# Picocopter_Edit.net
KiCad netlist of a schematic drawn in Altium Designer
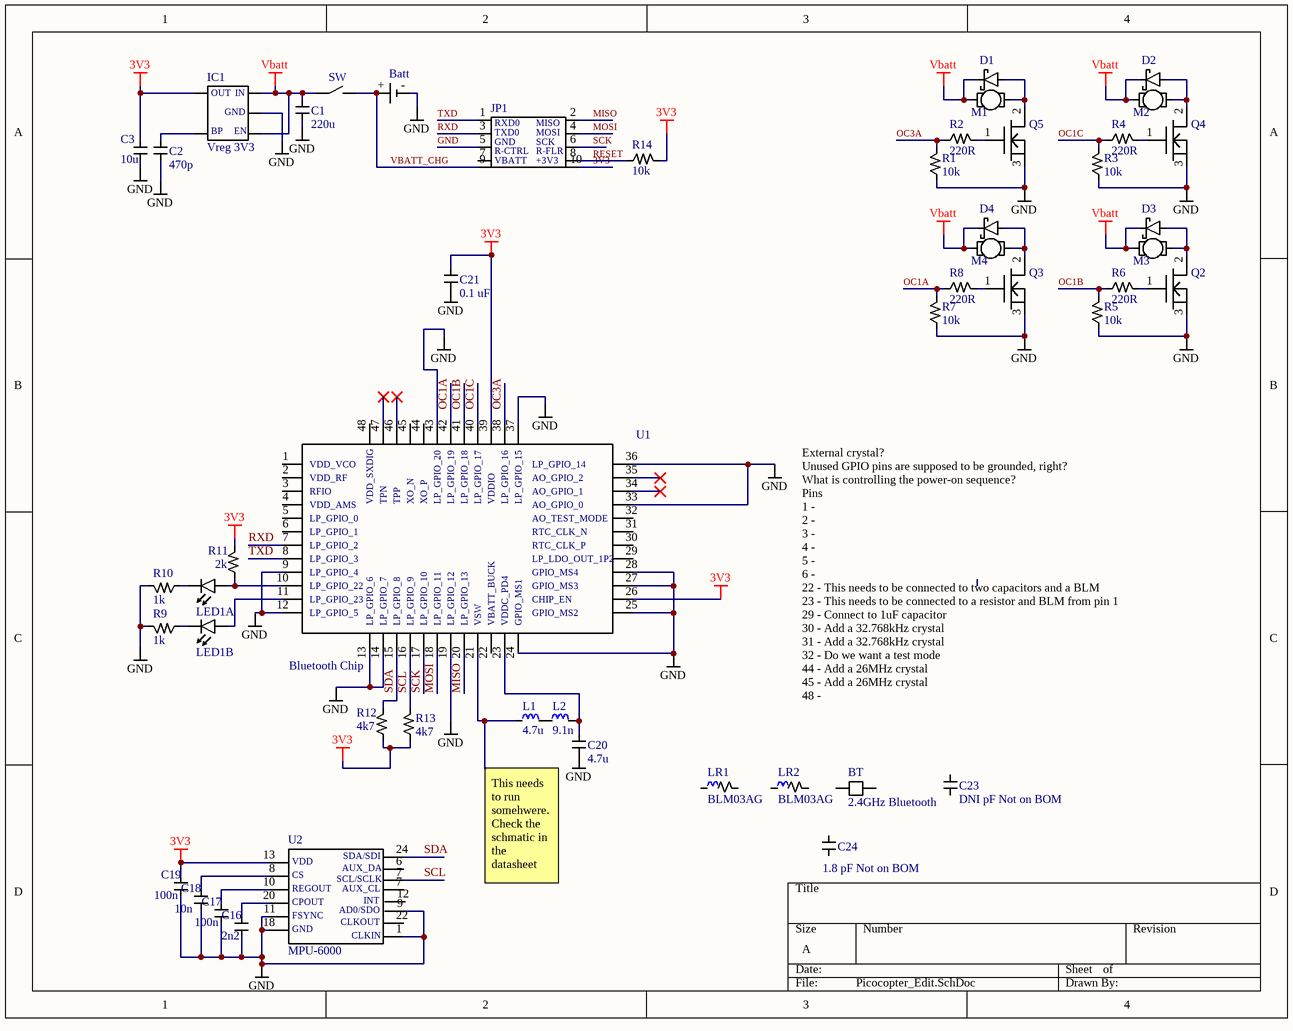
[diagram p0: Picocopter_Edit.SchDoc]

(export (version "E")
  (design (tool "Eeschema 10.0.6"))
  (components
    (comp (ref "Batt") (value "Battery") (footprint "Battery") (libsource (lib "Battery") (part "Battery")))
    (comp (ref "BT")
      (value "2.4GHz Bluetooth")
      (footprint "2.4GHz Bluetooth")
      (libsource (lib "2.4GHz Bluetooth") (part "2.4GHz Bluetooth"))
    )
    (comp (ref "C1")
      (value "220u")
      (footprint "1206 Capacitor")
      (libsource (lib "1206 Capacitor") (part "1206 Capacitor"))
    )
    (comp (ref "C2")
      (value "470p")
      (footprint "0201 Capacitor")
      (libsource (lib "0201 Capacitor") (part "10 pF Capacitor"))
    )
    (comp (ref "C3")
      (value "10u")
      (footprint "0402 Capacitor")
      (libsource (lib "0402 Capacitor") (part "0402 Capacitor"))
    )
    (comp (ref "C16")
      (value "2n2")
      (footprint "0603 Capacitor")
      (libsource (lib "0603 Capacitor") (part "0603 Capacitor"))
    )
    (comp (ref "C17")
      (value "100n")
      (footprint "0603 Capacitor")
      (libsource (lib "0603 Capacitor") (part "0603 Capacitor"))
    )
    (comp (ref "C18")
      (value "10n")
      (footprint "0603 Capacitor")
      (libsource (lib "0603 Capacitor") (part "0603 Capacitor"))
    )
    (comp (ref "C19")
      (value "100n")
      (footprint "0603 Capacitor")
      (libsource (lib "0603 Capacitor") (part "0603 Capacitor"))
    )
    (comp (ref "C20")
      (value "4.7u")
      (footprint "0603 Capacitor")
      (libsource (lib "0603 Capacitor") (part "0603 Capacitor"))
    )
    (comp (ref "C21")
      (value "0.1 uF")
      (footprint "0201 Capacitor")
      (libsource (lib "0201 Capacitor") (part "10 pF Capacitor"))
    )
    (comp (ref "C23")
      (value "DNI pF Not on BOM")
      (footprint "0201 Capacitor")
      (libsource (lib "0201 Capacitor") (part "10 pF Capacitor"))
    )
    (comp (ref "C24")
      (value "1.8 pF Not on BOM")
      (footprint "0201 Capacitor")
      (libsource (lib "0201 Capacitor") (part "10 pF Capacitor"))
    )
    (comp (ref "D1")
      (value "Schottky Diode")
      (footprint "Schottky Diode")
      (libsource (lib "Schottky Diode") (part "Schottky Diode"))
    )
    (comp (ref "D2")
      (value "Schottky Diode")
      (footprint "Schottky Diode")
      (libsource (lib "Schottky Diode") (part "Schottky Diode"))
    )
    (comp (ref "D3")
      (value "Schottky Diode")
      (footprint "Schottky Diode")
      (libsource (lib "Schottky Diode") (part "Schottky Diode"))
    )
    (comp (ref "D4")
      (value "Schottky Diode")
      (footprint "Schottky Diode")
      (libsource (lib "Schottky Diode") (part "Schottky Diode"))
    )
    (comp (ref "IC1")
      (value "Vreg 3V3")
      (footprint "Voltage Regulator")
      (libsource (lib "Voltage Regulator") (part "Voltage Regulator"))
    )
    (comp (ref "JP1")
      (value "10 Pin Connector")
      (footprint "10 Pin Connector")
      (libsource (lib "10 Pin Connector") (part "10 Pin Connector"))
    )
    (comp (ref "L1")
      (value "4.7u")
      (footprint "INDC2924X10N")
      (libsource (lib "1008 Inductor") (part "Component_1"))
    )
    (comp (ref "L2")
      (value "9.1n")
      (footprint "PCBComponent_1 - duplicate")
      (libsource (lib "0402 Inductor") (part "Component_1"))
    )
    (comp (ref "LED1A")
      (value "PicoLED")
      (footprint "DFN70P60X45-2N")
      (libsource (lib "PicoLED") (part "PicoLED"))
    )
    (comp (ref "LED1B")
      (value "PicoLED")
      (footprint "DFN70P60X45-2N")
      (libsource (lib "PicoLED") (part "PicoLED"))
    )
    (comp (ref "LR1")
      (value "BLM03AG")
      (footprint "INDC0603X10N")
      (libsource (lib "BLM03AG Resistive Inductor") (part "Component_1"))
    )
    (comp (ref "LR2")
      (value "BLM03AG")
      (footprint "INDC0603X10N")
      (libsource (lib "BLM03AG Resistive Inductor") (part "Component_1"))
    )
    (comp (ref "M1") (value "Motor") (footprint "Battery") (libsource (lib "Motor") (part "Motor")))
    (comp (ref "M2") (value "Motor") (footprint "Battery") (libsource (lib "Motor") (part "Motor")))
    (comp (ref "M3") (value "Motor") (footprint "Battery") (libsource (lib "Motor") (part "Motor")))
    (comp (ref "M4") (value "Motor") (footprint "Battery") (libsource (lib "Motor") (part "Motor")))
    (comp (ref "Q2")
      (value "N-Channel MOSFET")
      (footprint "N-Channel MOSFET")
      (libsource (lib "N-Channel MOSFET") (part "N-Channel MOSFET"))
    )
    (comp (ref "Q3")
      (value "N-Channel MOSFET")
      (footprint "N-Channel MOSFET")
      (libsource (lib "N-Channel MOSFET") (part "N-Channel MOSFET"))
    )
    (comp (ref "Q4")
      (value "N-Channel MOSFET")
      (footprint "N-Channel MOSFET")
      (libsource (lib "N-Channel MOSFET") (part "N-Channel MOSFET"))
    )
    (comp (ref "Q5")
      (value "MOSFET")
      (footprint "N-Channel MOSFET")
      (libsource (lib "N-Channel MOSFET") (part "N-Channel MOSFET"))
    )
    (comp (ref "R1")
      (value "10k")
      (footprint "0402 Resistor")
      (libsource (lib "0402 Resistor") (part "0402 Resistor"))
    )
    (comp (ref "R2")
      (value "220R")
      (footprint "0402 Resistor")
      (libsource (lib "0402 Resistor") (part "0402 Resistor"))
    )
    (comp (ref "R3")
      (value "10k")
      (footprint "0402 Resistor")
      (libsource (lib "0402 Resistor") (part "0402 Resistor"))
    )
    (comp (ref "R4")
      (value "220R")
      (footprint "0402 Resistor")
      (libsource (lib "0402 Resistor") (part "0402 Resistor"))
    )
    (comp (ref "R5")
      (value "10k")
      (footprint "0402 Resistor")
      (libsource (lib "0402 Resistor") (part "0402 Resistor"))
    )
    (comp (ref "R6")
      (value "220R")
      (footprint "0402 Resistor")
      (libsource (lib "0402 Resistor") (part "0402 Resistor"))
    )
    (comp (ref "R7")
      (value "10k")
      (footprint "0402 Resistor")
      (libsource (lib "0402 Resistor") (part "0402 Resistor"))
    )
    (comp (ref "R8")
      (value "220R")
      (footprint "0402 Resistor")
      (libsource (lib "0402 Resistor") (part "0402 Resistor"))
    )
    (comp (ref "R9")
      (value "1k")
      (footprint "0402 Resistor")
      (libsource (lib "0402 Resistor") (part "0402 Resistor"))
    )
    (comp (ref "R10")
      (value "1k")
      (footprint "0402 Resistor")
      (libsource (lib "0402 Resistor") (part "0402 Resistor"))
    )
    (comp (ref "R11")
      (value "2k")
      (footprint "0402 Resistor")
      (libsource (lib "0402 Resistor") (part "0402 Resistor"))
    )
    (comp (ref "R12")
      (value "4k7")
      (footprint "0402 Resistor")
      (libsource (lib "0402 Resistor") (part "0402 Resistor"))
    )
    (comp (ref "R13")
      (value "4k7")
      (footprint "0402 Resistor")
      (libsource (lib "0402 Resistor") (part "0402 Resistor"))
    )
    (comp (ref "R14")
      (value "10k")
      (footprint "0402 Resistor")
      (libsource (lib "0402 Resistor") (part "0402 Resistor"))
    )
    (comp (ref "SW")
      (value "2 Pin Header")
      (footprint "2 Pin Header")
      (libsource (lib "2 Pin Header") (part "2 Pin Header"))
    )
    (comp (ref "U1")
      (value "Bluetooth Chip")
      (footprint "QFN40P600X600X10_HS-49N")
      (libsource (lib "Bluetooth Chip") (part "Component_1"))
    )
    (comp (ref "U2")
      (value "MPU-6000")
      (footprint "Accelerometer")
      (libsource (lib "Accelerometer") (part "Accelerometer"))
    )
  )
  (nets
    (net (code "1") (name "/MISO") (class "Default")
      (node (ref "JP1") (pin "2") (pinfunction "2_2") (pintype "passive"))
      (node (ref "U1") (pin "20") (pinfunction "20_20") (pintype "passive"))
    )
    (net (code "2") (name "/MOSI") (class "Default")
      (node (ref "JP1") (pin "4") (pinfunction "4_4") (pintype "passive"))
      (node (ref "U1") (pin "18") (pinfunction "18_18") (pintype "passive"))
    )
    (net (code "3") (name "/OC1A") (class "Default")
      (node (ref "R7") (pin "2") (pinfunction "2_2") (pintype "passive"))
      (node (ref "R8") (pin "1") (pinfunction "1_1") (pintype "passive"))
      (node (ref "U1") (pin "42") (pinfunction "42_42") (pintype "passive"))
    )
    (net (code "4") (name "/OC1B") (class "Default")
      (node (ref "R5") (pin "2") (pinfunction "2_2") (pintype "passive"))
      (node (ref "R6") (pin "1") (pinfunction "1_1") (pintype "passive"))
      (node (ref "U1") (pin "41") (pinfunction "41_41") (pintype "passive"))
    )
    (net (code "5") (name "/OC1C") (class "Default")
      (node (ref "R3") (pin "2") (pinfunction "2_2") (pintype "passive"))
      (node (ref "R4") (pin "1") (pinfunction "1_1") (pintype "passive"))
      (node (ref "U1") (pin "40") (pinfunction "40_40") (pintype "passive"))
    )
    (net (code "6") (name "/OC3A") (class "Default")
      (node (ref "R1") (pin "2") (pinfunction "2_2") (pintype "passive"))
      (node (ref "R2") (pin "1") (pinfunction "1_1") (pintype "passive"))
      (node (ref "U1") (pin "38") (pinfunction "38_38") (pintype "passive"))
    )
    (net (code "7") (name "/RESET") (class "Default")
      (node (ref "JP1") (pin "8") (pinfunction "8_8") (pintype "passive"))
      (node (ref "R14") (pin "1") (pinfunction "1_1") (pintype "passive"))
    )
    (net (code "8") (name "/RXD") (class "Default")
      (node (ref "JP1") (pin "3") (pinfunction "3_3") (pintype "passive"))
      (node (ref "U1") (pin "7") (pinfunction "7_7") (pintype "passive"))
    )
    (net (code "9") (name "/SCK") (class "Default")
      (node (ref "JP1") (pin "6") (pinfunction "6_6") (pintype "passive"))
      (node (ref "U1") (pin "17") (pinfunction "17_17") (pintype "passive"))
    )
    (net (code "10") (name "/SCL") (class "Default")
      (node (ref "R13") (pin "2") (pinfunction "2_2") (pintype "passive"))
      (node (ref "U1") (pin "16") (pinfunction "16_16") (pintype "passive"))
      (node (ref "U2") (pin "7") (pinfunction "7_7") (pintype "passive"))
    )
    (net (code "11") (name "/SDA") (class "Default")
      (node (ref "R12") (pin "2") (pinfunction "2_2") (pintype "passive"))
      (node (ref "U1") (pin "15") (pinfunction "15_15") (pintype "passive"))
      (node (ref "U2") (pin "24") (pinfunction "24_24") (pintype "passive"))
    )
    (net (code "12") (name "/TXD") (class "Default")
      (node (ref "JP1") (pin "1") (pinfunction "1_1") (pintype "passive"))
      (node (ref "U1") (pin "8") (pinfunction "8_8") (pintype "passive"))
    )
    (net (code "13") (name "/VBATT_CHG") (class "Default")
      (node (ref "Batt") (pin "+") (pinfunction "7_+") (pintype "passive"))
      (node (ref "JP1") (pin "9") (pinfunction "9_9") (pintype "passive"))
      (node (ref "SW") (pin "6") (pinfunction "6_6") (pintype "passive"))
    )
    (net (code "14") (name "3V3") (class "Default")
      (node (ref "C19") (pin "2") (pinfunction "2_2") (pintype "passive"))
      (node (ref "C21") (pin "1") (pinfunction "1_1") (pintype "passive"))
      (node (ref "C3") (pin "2") (pinfunction "2_2") (pintype "passive"))
      (node (ref "IC1") (pin "1") (pinfunction "1_1") (pintype "passive"))
      (node (ref "JP1") (pin "10") (pinfunction "10_10") (pintype "passive"))
      (node (ref "R11") (pin "2") (pinfunction "2_2") (pintype "passive"))
      (node (ref "R12") (pin "1") (pinfunction "1_1") (pintype "passive"))
      (node (ref "R13") (pin "1") (pinfunction "1_1") (pintype "passive"))
      (node (ref "R14") (pin "2") (pinfunction "2_2") (pintype "passive"))
      (node (ref "U1") (pin "26") (pinfunction "26_26") (pintype "passive"))
      (node (ref "U1") (pin "39") (pinfunction "39_39") (pintype "passive"))
      (node (ref "U2") (pin "13") (pinfunction "13_13") (pintype "passive"))
    )
    (net (code "15") (name "GND") (class "Default")
      (node (ref "Batt") (pin "-") (pinfunction "8_-") (pintype "passive"))
      (node (ref "C1") (pin "1") (pinfunction "1_1") (pintype "passive"))
      (node (ref "C16") (pin "1") (pinfunction "1_1") (pintype "passive"))
      (node (ref "C17") (pin "1") (pinfunction "1_1") (pintype "passive"))
      (node (ref "C18") (pin "1") (pinfunction "1_1") (pintype "passive"))
      (node (ref "C19") (pin "1") (pinfunction "1_1") (pintype "passive"))
      (node (ref "C2") (pin "1") (pinfunction "1_1") (pintype "passive"))
      (node (ref "C20") (pin "1") (pinfunction "1_1") (pintype "passive"))
      (node (ref "C21") (pin "2") (pinfunction "2_2") (pintype "passive"))
      (node (ref "C3") (pin "1") (pinfunction "1_1") (pintype "passive"))
      (node (ref "IC1") (pin "4") (pinfunction "4_4") (pintype "passive"))
      (node (ref "JP1") (pin "5") (pinfunction "5_5") (pintype "passive"))
      (node (ref "Q2") (pin "3") (pinfunction "3_3") (pintype "passive"))
      (node (ref "Q3") (pin "3") (pinfunction "3_3") (pintype "passive"))
      (node (ref "Q4") (pin "3") (pinfunction "3_3") (pintype "passive"))
      (node (ref "Q5") (pin "3") (pinfunction "3_3") (pintype "passive"))
      (node (ref "R1") (pin "1") (pinfunction "1_1") (pintype "passive"))
      (node (ref "R10") (pin "2") (pinfunction "2_2") (pintype "passive"))
      (node (ref "R3") (pin "1") (pinfunction "1_1") (pintype "passive"))
      (node (ref "R5") (pin "1") (pinfunction "1_1") (pintype "passive"))
      (node (ref "R7") (pin "1") (pinfunction "1_1") (pintype "passive"))
      (node (ref "R9") (pin "2") (pinfunction "2_2") (pintype "passive"))
      (node (ref "U1") (pin "12") (pinfunction "12_12") (pintype "passive"))
      (node (ref "U1") (pin "13") (pinfunction "13_13") (pintype "passive"))
      (node (ref "U1") (pin "14") (pinfunction "14_14") (pintype "passive"))
      (node (ref "U1") (pin "19") (pinfunction "19_19") (pintype "passive"))
      (node (ref "U1") (pin "24") (pinfunction "24_24") (pintype "passive"))
      (node (ref "U1") (pin "25") (pinfunction "25_25") (pintype "passive"))
      (node (ref "U1") (pin "27") (pinfunction "27_27") (pintype "passive"))
      (node (ref "U1") (pin "28") (pinfunction "28_28") (pintype "passive"))
      (node (ref "U1") (pin "33") (pinfunction "33_33") (pintype "passive"))
      (node (ref "U1") (pin "36") (pinfunction "36_36") (pintype "passive"))
      (node (ref "U1") (pin "37") (pinfunction "37_37") (pintype "passive"))
      (node (ref "U1") (pin "43") (pinfunction "43_43") (pintype "passive"))
      (node (ref "U1") (pin "9") (pinfunction "9_9") (pintype "passive"))
      (node (ref "U2") (pin "1") (pinfunction "1_1") (pintype "passive"))
      (node (ref "U2") (pin "11") (pinfunction "11_11") (pintype "passive"))
      (node (ref "U2") (pin "18") (pinfunction "18_18") (pintype "passive"))
      (node (ref "U2") (pin "9") (pinfunction "9_9") (pintype "passive"))
    )
    (net (code "16") (name "Net-(C2-Pad2)") (class "Default")
      (node (ref "C2") (pin "2") (pinfunction "2_2") (pintype "passive"))
      (node (ref "IC1") (pin "2") (pinfunction "2_2") (pintype "passive"))
    )
    (net (code "17") (name "Net-(C16-Pad2)") (class "Default")
      (node (ref "C16") (pin "2") (pinfunction "2_2") (pintype "passive"))
      (node (ref "U2") (pin "20") (pinfunction "20_20") (pintype "passive"))
    )
    (net (code "18") (name "Net-(C17-Pad2)") (class "Default")
      (node (ref "C17") (pin "2") (pinfunction "2_2") (pintype "passive"))
      (node (ref "U2") (pin "10") (pinfunction "10_10") (pintype "passive"))
    )
    (net (code "19") (name "Net-(C18-Pad2)") (class "Default")
      (node (ref "C18") (pin "2") (pinfunction "2_2") (pintype "passive"))
      (node (ref "U2") (pin "8") (pinfunction "8_8") (pintype "passive"))
    )
    (net (code "20") (name "Net-(C20-Pad2)") (class "Default")
      (node (ref "C20") (pin "2") (pinfunction "2_2") (pintype "passive"))
      (node (ref "L2") (pin "0") (pinfunction "0_0") (pintype "passive"))
      (node (ref "U1") (pin "23") (pinfunction "23_23") (pintype "passive"))
    )
    (net (code "21") (name "Net-(D1-Pad1)") (class "Default")
      (node (ref "D1") (pin "1") (pinfunction "1_1") (pintype "passive"))
      (node (ref "M1") (pin "4") (pinfunction "4_4") (pintype "passive"))
      (node (ref "Q5") (pin "2") (pinfunction "2_2") (pintype "passive"))
    )
    (net (code "22") (name "Net-(D2-Pad1)") (class "Default")
      (node (ref "D2") (pin "1") (pinfunction "1_1") (pintype "passive"))
      (node (ref "M2") (pin "4") (pinfunction "4_4") (pintype "passive"))
      (node (ref "Q4") (pin "2") (pinfunction "2_2") (pintype "passive"))
    )
    (net (code "23") (name "Net-(D3-Pad1)") (class "Default")
      (node (ref "D3") (pin "1") (pinfunction "1_1") (pintype "passive"))
      (node (ref "M3") (pin "4") (pinfunction "4_4") (pintype "passive"))
      (node (ref "Q2") (pin "2") (pinfunction "2_2") (pintype "passive"))
    )
    (net (code "24") (name "Net-(D4-Pad1)") (class "Default")
      (node (ref "D4") (pin "1") (pinfunction "1_1") (pintype "passive"))
      (node (ref "M4") (pin "4") (pinfunction "4_4") (pintype "passive"))
      (node (ref "Q3") (pin "2") (pinfunction "2_2") (pintype "passive"))
    )
    (net (code "25") (name "Net-(L1-Pad0)") (class "Default")
      (node (ref "L1") (pin "0") (pinfunction "0_0") (pintype "passive"))
      (node (ref "L2") (pin "1") (pinfunction "1_1") (pintype "passive"))
    )
    (net (code "26") (name "Net-(L1-Pad1)") (class "Default")
      (node (ref "L1") (pin "1") (pinfunction "1_1") (pintype "passive"))
      (node (ref "U1") (pin "21") (pinfunction "21_21") (pintype "passive"))
    )
    (net (code "27") (name "Net-(LED1A-Pad1)") (class "Default")
      (node (ref "LED1A") (pin "1") (pinfunction "1_1") (pintype "passive"))
      (node (ref "R11") (pin "1") (pinfunction "1_1") (pintype "passive"))
      (node (ref "U1") (pin "10") (pinfunction "10_10") (pintype "passive"))
    )
    (net (code "28") (name "Net-(LED1A-Pad2)") (class "Default")
      (node (ref "LED1A") (pin "2") (pinfunction "2_2") (pintype "passive"))
      (node (ref "R10") (pin "1") (pinfunction "1_1") (pintype "passive"))
    )
    (net (code "29") (name "Net-(LED1B-Pad1)") (class "Default")
      (node (ref "LED1B") (pin "1") (pinfunction "1_1") (pintype "passive"))
      (node (ref "U1") (pin "11") (pinfunction "11_11") (pintype "passive"))
    )
    (net (code "30") (name "Net-(LED1B-Pad2)") (class "Default")
      (node (ref "LED1B") (pin "2") (pinfunction "2_2") (pintype "passive"))
      (node (ref "R9") (pin "1") (pinfunction "1_1") (pintype "passive"))
    )
    (net (code "31") (name "Net-(Q2-Pad1)") (class "Default")
      (node (ref "Q2") (pin "1") (pinfunction "1_1") (pintype "passive"))
      (node (ref "R6") (pin "2") (pinfunction "2_2") (pintype "passive"))
    )
    (net (code "32") (name "Net-(Q3-Pad1)") (class "Default")
      (node (ref "Q3") (pin "1") (pinfunction "1_1") (pintype "passive"))
      (node (ref "R8") (pin "2") (pinfunction "2_2") (pintype "passive"))
    )
    (net (code "33") (name "Net-(Q4-Pad1)") (class "Default")
      (node (ref "Q4") (pin "1") (pinfunction "1_1") (pintype "passive"))
      (node (ref "R4") (pin "2") (pinfunction "2_2") (pintype "passive"))
    )
    (net (code "34") (name "Net-(Q5-Pad1)") (class "Default")
      (node (ref "Q5") (pin "1") (pinfunction "1_1") (pintype "passive"))
      (node (ref "R2") (pin "2") (pinfunction "2_2") (pintype "passive"))
    )
    (net (code "35") (name "Vbatt") (class "Default")
      (node (ref "C1") (pin "2") (pinfunction "2_2") (pintype "passive"))
      (node (ref "D1") (pin "2") (pinfunction "2_2") (pintype "passive"))
      (node (ref "D2") (pin "2") (pinfunction "2_2") (pintype "passive"))
      (node (ref "D3") (pin "2") (pinfunction "2_2") (pintype "passive"))
      (node (ref "D4") (pin "2") (pinfunction "2_2") (pintype "passive"))
      (node (ref "IC1") (pin "3") (pinfunction "3_3") (pintype "passive"))
      (node (ref "IC1") (pin "5") (pinfunction "5_5") (pintype "passive"))
      (node (ref "M1") (pin "3") (pinfunction "3_3") (pintype "passive"))
      (node (ref "M2") (pin "3") (pinfunction "3_3") (pintype "passive"))
      (node (ref "M3") (pin "3") (pinfunction "3_3") (pintype "passive"))
      (node (ref "M4") (pin "3") (pinfunction "3_3") (pintype "passive"))
      (node (ref "SW") (pin "5") (pinfunction "5_5") (pintype "passive"))
    )
    (net (code "36") (name "unconnected-(BT-Pad1)") (class "Default")
      (node (ref "BT") (pin "1") (pinfunction "1_1") (pintype "passive"))
    )
    (net (code "37") (name "unconnected-(BT-Pad2)") (class "Default")
      (node (ref "BT") (pin "2") (pinfunction "2_2") (pintype "passive"))
    )
    (net (code "38") (name "unconnected-(C23-Pad1)") (class "Default")
      (node (ref "C23") (pin "1") (pinfunction "1_1") (pintype "passive"))
    )
    (net (code "39") (name "unconnected-(C23-Pad2)") (class "Default")
      (node (ref "C23") (pin "2") (pinfunction "2_2") (pintype "passive"))
    )
    (net (code "40") (name "unconnected-(C24-Pad1)") (class "Default")
      (node (ref "C24") (pin "1") (pinfunction "1_1") (pintype "passive"))
    )
    (net (code "41") (name "unconnected-(C24-Pad2)") (class "Default")
      (node (ref "C24") (pin "2") (pinfunction "2_2") (pintype "passive"))
    )
    (net (code "42") (name "unconnected-(JP1-Pad7)") (class "Default")
      (node (ref "JP1") (pin "7") (pinfunction "7_7") (pintype "passive"))
    )
    (net (code "43") (name "unconnected-(LR1-Pad0)") (class "Default")
      (node (ref "LR1") (pin "0") (pinfunction "0_0") (pintype "passive"))
    )
    (net (code "44") (name "unconnected-(LR1-Pad1)") (class "Default")
      (node (ref "LR1") (pin "1") (pinfunction "1_1") (pintype "passive"))
    )
    (net (code "45") (name "unconnected-(LR2-Pad0)") (class "Default")
      (node (ref "LR2") (pin "0") (pinfunction "0_0") (pintype "passive"))
    )
    (net (code "46") (name "unconnected-(LR2-Pad1)") (class "Default")
      (node (ref "LR2") (pin "1") (pinfunction "1_1") (pintype "passive"))
    )
    (net (code "47") (name "unconnected-(U1-Pad1)") (class "Default")
      (node (ref "U1") (pin "1") (pinfunction "1_1") (pintype "passive"))
    )
    (net (code "48") (name "unconnected-(U1-Pad2)") (class "Default")
      (node (ref "U1") (pin "2") (pinfunction "2_2") (pintype "passive"))
    )
    (net (code "49") (name "unconnected-(U1-Pad3)") (class "Default")
      (node (ref "U1") (pin "3") (pinfunction "3_3") (pintype "passive"))
    )
    (net (code "50") (name "unconnected-(U1-Pad4)") (class "Default")
      (node (ref "U1") (pin "4") (pinfunction "4_4") (pintype "passive"))
    )
    (net (code "51") (name "unconnected-(U1-Pad5)") (class "Default")
      (node (ref "U1") (pin "5") (pinfunction "5_5") (pintype "passive"))
    )
    (net (code "52") (name "unconnected-(U1-Pad6)") (class "Default")
      (node (ref "U1") (pin "6") (pinfunction "6_6") (pintype "passive"))
    )
    (net (code "53") (name "unconnected-(U1-Pad22)") (class "Default")
      (node (ref "U1") (pin "22") (pinfunction "22_22") (pintype "passive"))
    )
    (net (code "54") (name "unconnected-(U1-Pad29)") (class "Default")
      (node (ref "U1") (pin "29") (pinfunction "29_29") (pintype "passive"))
    )
    (net (code "55") (name "unconnected-(U1-Pad30)") (class "Default")
      (node (ref "U1") (pin "30") (pinfunction "30_30") (pintype "passive"))
    )
    (net (code "56") (name "unconnected-(U1-Pad31)") (class "Default")
      (node (ref "U1") (pin "31") (pinfunction "31_31") (pintype "passive"))
    )
    (net (code "57") (name "unconnected-(U1-Pad32)") (class "Default")
      (node (ref "U1") (pin "32") (pinfunction "32_32") (pintype "passive"))
    )
    (net (code "58") (name "unconnected-(U1-Pad34)") (class "Default")
      (node (ref "U1") (pin "34") (pinfunction "34_34") (pintype "passive+no_connect"))
    )
    (net (code "59") (name "unconnected-(U1-Pad35)") (class "Default")
      (node (ref "U1") (pin "35") (pinfunction "35_35") (pintype "passive+no_connect"))
    )
    (net (code "60") (name "unconnected-(U1-Pad44)") (class "Default")
      (node (ref "U1") (pin "44") (pinfunction "44_44") (pintype "passive"))
    )
    (net (code "61") (name "unconnected-(U1-Pad45)") (class "Default")
      (node (ref "U1") (pin "45") (pinfunction "45_45") (pintype "passive"))
    )
    (net (code "62") (name "unconnected-(U1-Pad46)") (class "Default")
      (node (ref "U1") (pin "46") (pinfunction "46_46") (pintype "passive+no_connect"))
    )
    (net (code "63") (name "unconnected-(U1-Pad47)") (class "Default")
      (node (ref "U1") (pin "47") (pinfunction "47_47") (pintype "passive+no_connect"))
    )
    (net (code "64") (name "unconnected-(U1-Pad48)") (class "Default")
      (node (ref "U1") (pin "48") (pinfunction "48_48") (pintype "passive"))
    )
    (net (code "65") (name "unconnected-(U2-Pad6)") (class "Default")
      (node (ref "U2") (pin "6") (pinfunction "6_6") (pintype "passive"))
    )
    (net (code "66") (name "unconnected-(U2-Pad7)") (class "Default")
      (node (ref "U2") (pin "7") (pinfunction "7_7") (pintype "passive"))
    )
    (net (code "67") (name "unconnected-(U2-Pad12)") (class "Default")
      (node (ref "U2") (pin "12") (pinfunction "12_12") (pintype "passive"))
    )
    (net (code "68") (name "unconnected-(U2-Pad22)") (class "Default")
      (node (ref "U2") (pin "22") (pinfunction "22_22") (pintype "passive"))
    )
  )
)
